# LEDTestBrd.net
KiCad netlist of a schematic drawn in EAGLE
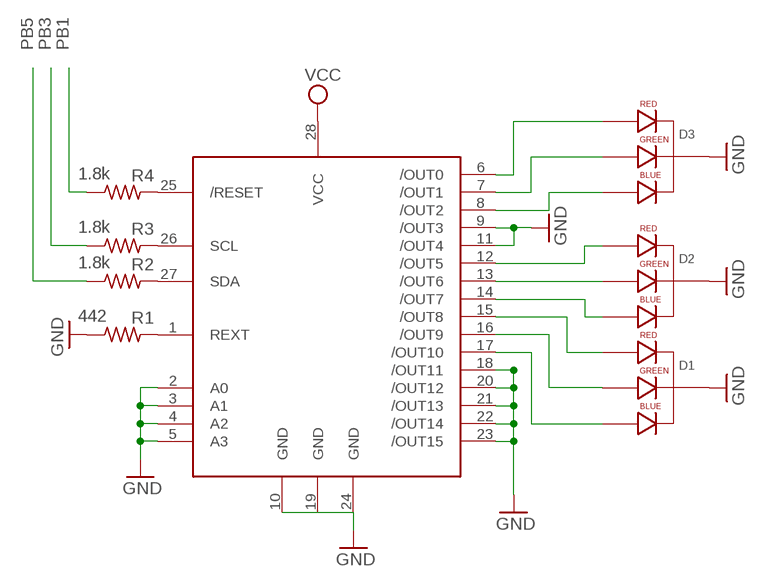
[diagram p0: schematic, sheet 1]

(export (version "E")
  (design (tool "Eeschema 10.0.6"))
  (components
    (comp (ref "D1")
      (value "LED-RGB-CC-THRUCLEAR")
      (footprint "eagle-import:LED-RGB-THRU")
      (libsource (lib "eagle-import") (part "LED-RGB-CC-THRUCLEAR"))
    )
    (comp (ref "D2")
      (value "LED-RGB-CC-THRUCLEAR")
      (footprint "eagle-import:LED-RGB-THRU")
      (libsource (lib "eagle-import") (part "LED-RGB-CC-THRUCLEAR"))
    )
    (comp (ref "D3")
      (value "LED-RGB-CC-THRUCLEAR")
      (footprint "eagle-import:LED-RGB-THRU")
      (libsource (lib "eagle-import") (part "LED-RGB-CC-THRUCLEAR"))
    )
    (comp (ref "R1")
      (value "442")
      (footprint "eagle-import:R0402")
      (libsource (lib "eagle-import") (part "R-US_R0402"))
    )
    (comp (ref "R2")
      (value "1.8k")
      (footprint "eagle-import:R0402")
      (libsource (lib "eagle-import") (part "R-US_R0402"))
    )
    (comp (ref "R3")
      (value "1.8k")
      (footprint "eagle-import:R0402")
      (libsource (lib "eagle-import") (part "R-US_R0402"))
    )
    (comp (ref "R4")
      (value "1.8k")
      (footprint "eagle-import:R0402")
      (libsource (lib "eagle-import") (part "R-US_R0402"))
    )
    (comp (ref "U$2")
      (value "TLC59116")
      (footprint "eagle-import:TSSOP28")
      (libsource (lib "eagle-import") (part "TLC59116"))
    )
  )
  (nets
    (net (code "1") (name "/PB1") (class "Default")
      (node (ref "R4") (pin "1") (pinfunction "1_1") (pintype "passive"))
    )
    (net (code "2") (name "/PB3") (class "Default")
      (node (ref "R3") (pin "1") (pinfunction "1_1") (pintype "passive"))
    )
    (net (code "3") (name "/PB5") (class "Default")
      (node (ref "R2") (pin "1") (pinfunction "1_1") (pintype "passive"))
    )
    (net (code "4") (name "GND") (class "Default")
      (node (ref "D1") (pin "2") (pinfunction "CATHODE_2") (pintype "bidirectional"))
      (node (ref "D2") (pin "2") (pinfunction "CATHODE_2") (pintype "bidirectional"))
      (node (ref "D3") (pin "2") (pinfunction "CATHODE_2") (pintype "bidirectional"))
      (node (ref "R1") (pin "1") (pinfunction "1_1") (pintype "passive"))
      (node (ref "U$2") (pin "10") (pinfunction "GND_10") (pintype "bidirectional"))
      (node (ref "U$2") (pin "11") (pinfunction "/OUT4_11") (pintype "bidirectional"))
      (node (ref "U$2") (pin "18") (pinfunction "/OUT11_18") (pintype "bidirectional"))
      (node (ref "U$2") (pin "19") (pinfunction "GND_19") (pintype "bidirectional"))
      (node (ref "U$2") (pin "2") (pinfunction "A0_2") (pintype "bidirectional"))
      (node (ref "U$2") (pin "20") (pinfunction "/OUT12_20") (pintype "bidirectional"))
      (node (ref "U$2") (pin "21") (pinfunction "/OUT13_21") (pintype "bidirectional"))
      (node (ref "U$2") (pin "22") (pinfunction "/OUT14_22") (pintype "bidirectional"))
      (node (ref "U$2") (pin "23") (pinfunction "/OUT15_23") (pintype "bidirectional"))
      (node (ref "U$2") (pin "24") (pinfunction "GND_24") (pintype "bidirectional"))
      (node (ref "U$2") (pin "3") (pinfunction "A1_3") (pintype "bidirectional"))
      (node (ref "U$2") (pin "4") (pinfunction "A2_4") (pintype "bidirectional"))
      (node (ref "U$2") (pin "5") (pinfunction "A3_5") (pintype "bidirectional"))
      (node (ref "U$2") (pin "9") (pinfunction "/OUT3_9") (pintype "bidirectional"))
    )
    (net (code "5") (name "Net-(D1-BLUE_CATHODE)") (class "Default")
      (node (ref "D1") (pin "4") (pinfunction "BLUE_CATHODE_4") (pintype "bidirectional"))
      (node (ref "U$2") (pin "17") (pinfunction "/OUT10_17") (pintype "bidirectional"))
    )
    (net (code "6") (name "Net-(D1-GREEN_CATHODE)") (class "Default")
      (node (ref "D1") (pin "3") (pinfunction "GREEN_CATHODE_3") (pintype "bidirectional"))
      (node (ref "U$2") (pin "16") (pinfunction "/OUT9_16") (pintype "bidirectional"))
    )
    (net (code "7") (name "Net-(D1-RED_CATHODE)") (class "Default")
      (node (ref "D1") (pin "1") (pinfunction "RED_CATHODE_1") (pintype "bidirectional"))
      (node (ref "U$2") (pin "15") (pinfunction "/OUT8_15") (pintype "bidirectional"))
    )
    (net (code "8") (name "Net-(D2-BLUE_CATHODE)") (class "Default")
      (node (ref "D2") (pin "4") (pinfunction "BLUE_CATHODE_4") (pintype "bidirectional"))
      (node (ref "U$2") (pin "14") (pinfunction "/OUT7_14") (pintype "bidirectional"))
    )
    (net (code "9") (name "Net-(D2-GREEN_CATHODE)") (class "Default")
      (node (ref "D2") (pin "3") (pinfunction "GREEN_CATHODE_3") (pintype "bidirectional"))
      (node (ref "U$2") (pin "13") (pinfunction "/OUT6_13") (pintype "bidirectional"))
    )
    (net (code "10") (name "Net-(D2-RED_CATHODE)") (class "Default")
      (node (ref "D2") (pin "1") (pinfunction "RED_CATHODE_1") (pintype "bidirectional"))
      (node (ref "U$2") (pin "12") (pinfunction "/OUT5_12") (pintype "bidirectional"))
    )
    (net (code "11") (name "Net-(D3-BLUE_CATHODE)") (class "Default")
      (node (ref "D3") (pin "4") (pinfunction "BLUE_CATHODE_4") (pintype "bidirectional"))
      (node (ref "U$2") (pin "8") (pinfunction "/OUT2_8") (pintype "bidirectional"))
    )
    (net (code "12") (name "Net-(D3-GREEN_CATHODE)") (class "Default")
      (node (ref "D3") (pin "3") (pinfunction "GREEN_CATHODE_3") (pintype "bidirectional"))
      (node (ref "U$2") (pin "7") (pinfunction "/OUT1_7") (pintype "bidirectional"))
    )
    (net (code "13") (name "Net-(D3-RED_CATHODE)") (class "Default")
      (node (ref "D3") (pin "1") (pinfunction "RED_CATHODE_1") (pintype "bidirectional"))
      (node (ref "U$2") (pin "6") (pinfunction "/OUT0_6") (pintype "bidirectional"))
    )
    (net (code "14") (name "Net-(U$2-REXT)") (class "Default")
      (node (ref "R1") (pin "2") (pinfunction "2_2") (pintype "passive"))
      (node (ref "U$2") (pin "1") (pinfunction "REXT_1") (pintype "bidirectional"))
    )
    (net (code "15") (name "Net-(U$2-SCL)") (class "Default")
      (node (ref "R3") (pin "2") (pinfunction "2_2") (pintype "passive"))
      (node (ref "U$2") (pin "26") (pinfunction "SCL_26") (pintype "bidirectional"))
    )
    (net (code "16") (name "Net-(U$2-SDA)") (class "Default")
      (node (ref "R2") (pin "2") (pinfunction "2_2") (pintype "passive"))
      (node (ref "U$2") (pin "27") (pinfunction "SDA_27") (pintype "bidirectional"))
    )
    (net (code "17") (name "Net-(U$2-{slash}RESET)") (class "Default")
      (node (ref "R4") (pin "2") (pinfunction "2_2") (pintype "passive"))
      (node (ref "U$2") (pin "25") (pinfunction "/RESET_25") (pintype "bidirectional"))
    )
    (net (code "18") (name "VCC") (class "Default")
      (node (ref "U$2") (pin "28") (pinfunction "VCC_28") (pintype "bidirectional"))
    )
  )
)
